# 12-pin_SOIC_TSSOP.net
KiCad netlist of a schematic drawn in EAGLE
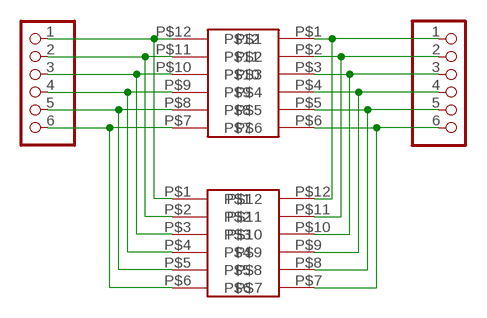
[diagram p0: schematic, sheet 1]

(export (version "E")
  (design (tool "Eeschema 10.0.6"))
  (components
    (comp (ref "JP1")
      (value "PADS-6")
      (footprint "eagle-import:PADS-6")
      (libsource (lib "eagle-import") (part "PADS-6"))
    )
    (comp (ref "JP2")
      (value "PADS-6")
      (footprint "eagle-import:PADS-6")
      (libsource (lib "eagle-import") (part "PADS-6"))
    )
    (comp (ref "U$1")
      (value "12-PINTSSOP-NW")
      (footprint "eagle-import:TSSOP12-NW")
      (libsource (lib "eagle-import") (part "12-PINTSSOP-NW"))
    )
    (comp (ref "U$2")
      (value "12-PINSOIC-NW")
      (footprint "eagle-import:SO12-NW")
      (libsource (lib "eagle-import") (part "12-PINSOIC-NW"))
    )
  )
  (nets
    (net (code "1") (name "Net-(JP1-Pad1)") (class "Default")
      (node (ref "JP1") (pin "1") (pinfunction "1_1") (pintype "passive"))
      (node (ref "U$1") (pin "P$1") (pinfunction "P$1_P$1") (pintype "bidirectional"))
      (node (ref "U$2") (pin "P$12") (pinfunction "P$12_P$12") (pintype "bidirectional"))
    )
    (net (code "2") (name "Net-(JP1-Pad2)") (class "Default")
      (node (ref "JP1") (pin "2") (pinfunction "2_2") (pintype "passive"))
      (node (ref "U$1") (pin "P$2") (pinfunction "P$2_P$2") (pintype "bidirectional"))
      (node (ref "U$2") (pin "P$11") (pinfunction "P$11_P$11") (pintype "bidirectional"))
    )
    (net (code "3") (name "Net-(JP1-Pad3)") (class "Default")
      (node (ref "JP1") (pin "3") (pinfunction "3_3") (pintype "passive"))
      (node (ref "U$1") (pin "P$3") (pinfunction "P$3_P$3") (pintype "bidirectional"))
      (node (ref "U$2") (pin "P$10") (pinfunction "P$10_P$10") (pintype "bidirectional"))
    )
    (net (code "4") (name "Net-(JP1-Pad4)") (class "Default")
      (node (ref "JP1") (pin "4") (pinfunction "4_4") (pintype "passive"))
      (node (ref "U$1") (pin "P$4") (pinfunction "P$4_P$4") (pintype "bidirectional"))
      (node (ref "U$2") (pin "P$9") (pinfunction "P$9_P$9") (pintype "bidirectional"))
    )
    (net (code "5") (name "Net-(JP1-Pad5)") (class "Default")
      (node (ref "JP1") (pin "5") (pinfunction "5_5") (pintype "passive"))
      (node (ref "U$1") (pin "P$5") (pinfunction "P$5_P$5") (pintype "bidirectional"))
      (node (ref "U$2") (pin "P$8") (pinfunction "P$8_P$8") (pintype "bidirectional"))
    )
    (net (code "6") (name "Net-(JP1-Pad6)") (class "Default")
      (node (ref "JP1") (pin "6") (pinfunction "6_6") (pintype "passive"))
      (node (ref "U$1") (pin "P$6") (pinfunction "P$6_P$6") (pintype "bidirectional"))
      (node (ref "U$2") (pin "P$7") (pinfunction "P$7_P$7") (pintype "bidirectional"))
    )
    (net (code "7") (name "Net-(JP2-Pad1)") (class "Default")
      (node (ref "JP2") (pin "1") (pinfunction "1_1") (pintype "passive"))
      (node (ref "U$1") (pin "P$12") (pinfunction "P$12_P$12") (pintype "bidirectional"))
      (node (ref "U$2") (pin "P$1") (pinfunction "P$1_P$1") (pintype "bidirectional"))
    )
    (net (code "8") (name "Net-(JP2-Pad2)") (class "Default")
      (node (ref "JP2") (pin "2") (pinfunction "2_2") (pintype "passive"))
      (node (ref "U$1") (pin "P$11") (pinfunction "P$11_P$11") (pintype "bidirectional"))
      (node (ref "U$2") (pin "P$2") (pinfunction "P$2_P$2") (pintype "bidirectional"))
    )
    (net (code "9") (name "Net-(JP2-Pad3)") (class "Default")
      (node (ref "JP2") (pin "3") (pinfunction "3_3") (pintype "passive"))
      (node (ref "U$1") (pin "P$10") (pinfunction "P$10_P$10") (pintype "bidirectional"))
      (node (ref "U$2") (pin "P$3") (pinfunction "P$3_P$3") (pintype "bidirectional"))
    )
    (net (code "10") (name "Net-(JP2-Pad4)") (class "Default")
      (node (ref "JP2") (pin "4") (pinfunction "4_4") (pintype "passive"))
      (node (ref "U$1") (pin "P$9") (pinfunction "P$9_P$9") (pintype "bidirectional"))
      (node (ref "U$2") (pin "P$4") (pinfunction "P$4_P$4") (pintype "bidirectional"))
    )
    (net (code "11") (name "Net-(JP2-Pad5)") (class "Default")
      (node (ref "JP2") (pin "5") (pinfunction "5_5") (pintype "passive"))
      (node (ref "U$1") (pin "P$8") (pinfunction "P$8_P$8") (pintype "bidirectional"))
      (node (ref "U$2") (pin "P$5") (pinfunction "P$5_P$5") (pintype "bidirectional"))
    )
    (net (code "12") (name "Net-(JP2-Pad6)") (class "Default")
      (node (ref "JP2") (pin "6") (pinfunction "6_6") (pintype "passive"))
      (node (ref "U$1") (pin "P$7") (pinfunction "P$7_P$7") (pintype "bidirectional"))
      (node (ref "U$2") (pin "P$6") (pinfunction "P$6_P$6") (pintype "bidirectional"))
    )
  )
)
